# 2_Motors_V2.net
KiCad netlist of a schematic drawn in EAGLE
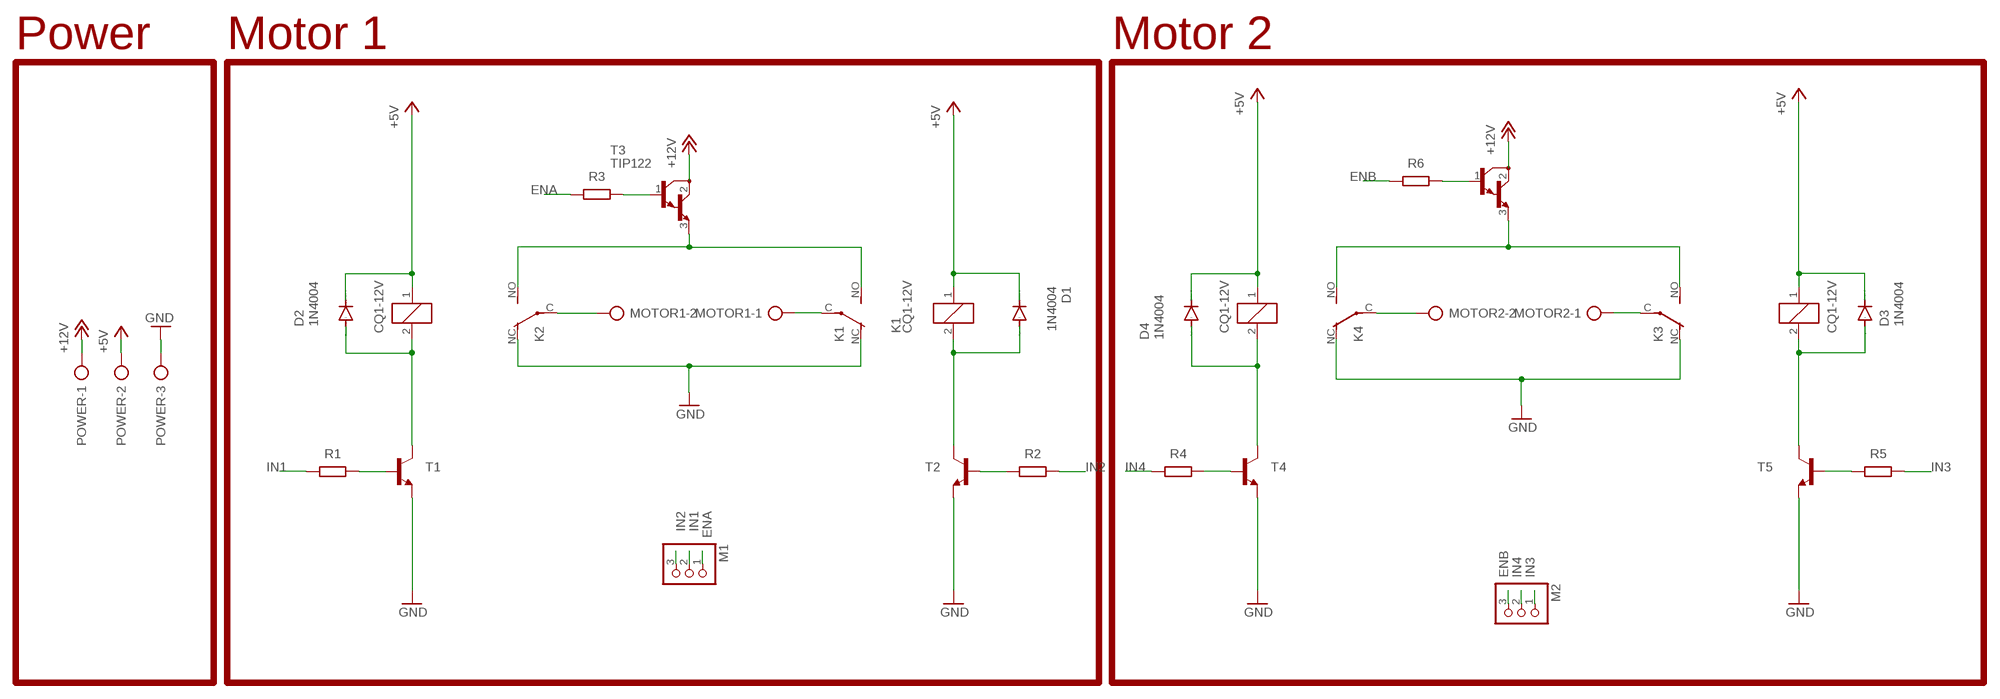
[diagram p0: schematic, sheet 1]

(export (version "E")
  (design (tool "Eeschema 10.0.6"))
  (components
    (comp (ref "D1")
      (value "1N4004")
      (footprint "eagle-import:DO41-10")
      (libsource (lib "eagle-import") (part "1N4004"))
    )
    (comp (ref "D2")
      (value "1N4004")
      (footprint "eagle-import:DO41-10")
      (libsource (lib "eagle-import") (part "1N4004"))
    )
    (comp (ref "D3")
      (value "1N4004")
      (footprint "eagle-import:DO41-10")
      (libsource (lib "eagle-import") (part "1N4004"))
    )
    (comp (ref "D4")
      (value "1N4004")
      (footprint "eagle-import:DO41-10")
      (libsource (lib "eagle-import") (part "1N4004"))
    )
    (comp (ref "K1")
      (value "CQ1-12V")
      (footprint "eagle-import:CQ1")
      (libsource (lib "eagle-import") (part "CQ1-12V"))
    )
    (comp (ref "K2")
      (value "CQ1-12V")
      (footprint "eagle-import:CQ1")
      (libsource (lib "eagle-import") (part "CQ1-12V"))
    )
    (comp (ref "K3")
      (value "CQ1-12V")
      (footprint "eagle-import:CQ1")
      (libsource (lib "eagle-import") (part "CQ1-12V"))
    )
    (comp (ref "K4")
      (value "CQ1-12V")
      (footprint "eagle-import:CQ1")
      (libsource (lib "eagle-import") (part "CQ1-12V"))
    )
    (comp (ref "M1")
      (value "PINHD-1X3")
      (footprint "eagle-import:1X03")
      (libsource (lib "eagle-import") (part "PINHD-1X3"))
    )
    (comp (ref "M2")
      (value "PINHD-1X3")
      (footprint "eagle-import:1X03")
      (libsource (lib "eagle-import") (part "PINHD-1X3"))
    )
    (comp (ref "MOTOR1")
      (value "AK300/2")
      (footprint "eagle-import:AK300_2")
      (libsource (lib "eagle-import") (part "AK300/2"))
    )
    (comp (ref "MOTOR2")
      (value "AK300/2")
      (footprint "eagle-import:AK300_2")
      (libsource (lib "eagle-import") (part "AK300/2"))
    )
    (comp (ref "POWER")
      (value "AK300/3")
      (footprint "eagle-import:AK300_3")
      (libsource (lib "eagle-import") (part "AK300/3"))
    )
    (comp (ref "R1")
      (value "4.7k")
      (footprint "eagle-import:0204_7")
      (libsource (lib "eagle-import") (part "R-EU_0204/7"))
    )
    (comp (ref "R2")
      (value "4.7k")
      (footprint "eagle-import:0204_7")
      (libsource (lib "eagle-import") (part "R-EU_0204/7"))
    )
    (comp (ref "R3")
      (value "4.7k")
      (footprint "eagle-import:0204_7")
      (libsource (lib "eagle-import") (part "R-EU_0204/7"))
    )
    (comp (ref "R4")
      (value "4.7k")
      (footprint "eagle-import:0204_7")
      (libsource (lib "eagle-import") (part "R-EU_0204/7"))
    )
    (comp (ref "R5")
      (value "4.7k")
      (footprint "eagle-import:0204_7")
      (libsource (lib "eagle-import") (part "R-EU_0204/7"))
    )
    (comp (ref "R6")
      (value "4.7k")
      (footprint "eagle-import:0204_7")
      (libsource (lib "eagle-import") (part "R-EU_0204/7"))
    )
    (comp (ref "T1")
      (value "2N2222-NPN-TO92-EBC")
      (footprint "eagle-import:TO92-EBC")
      (libsource (lib "eagle-import") (part "-NPN-TO92-EBC2N2222"))
    )
    (comp (ref "T2")
      (value "2N2222-NPN-TO92-EBC")
      (footprint "eagle-import:TO92-EBC")
      (libsource (lib "eagle-import") (part "-NPN-TO92-EBC2N2222"))
    )
    (comp (ref "T3")
      (value "TIP122")
      (footprint "eagle-import:TO220")
      (libsource (lib "eagle-import") (part "TIP122"))
    )
    (comp (ref "T4")
      (value "2N2222-NPN-TO92-EBC")
      (footprint "eagle-import:TO92-EBC")
      (libsource (lib "eagle-import") (part "-NPN-TO92-EBC2N2222"))
    )
    (comp (ref "T5")
      (value "2N2222-NPN-TO92-EBC")
      (footprint "eagle-import:TO92-EBC")
      (libsource (lib "eagle-import") (part "-NPN-TO92-EBC2N2222"))
    )
    (comp (ref "T6")
      (value "TIP122")
      (footprint "eagle-import:TO220")
      (libsource (lib "eagle-import") (part "TIP122"))
    )
  )
  (nets
    (net (code "1") (name "+5V") (class "Default")
      (node (ref "D1") (pin "C") (pinfunction "C_C") (pintype "passive"))
      (node (ref "D2") (pin "C") (pinfunction "C_C") (pintype "passive"))
      (node (ref "D3") (pin "C") (pinfunction "C_C") (pintype "passive"))
      (node (ref "D4") (pin "C") (pinfunction "C_C") (pintype "passive"))
      (node (ref "K1") (pin "1") (pinfunction "1_1") (pintype "passive"))
      (node (ref "K2") (pin "1") (pinfunction "1_1") (pintype "passive"))
      (node (ref "K3") (pin "1") (pinfunction "1_1") (pintype "passive"))
      (node (ref "K4") (pin "1") (pinfunction "1_1") (pintype "passive"))
      (node (ref "POWER") (pin "2") (pinfunction "KL_2") (pintype "passive"))
    )
    (net (code "2") (name "+12V") (class "Default")
      (node (ref "POWER") (pin "1") (pinfunction "KL_1") (pintype "passive"))
      (node (ref "T3") (pin "2") (pinfunction "C_2") (pintype "passive"))
      (node (ref "T6") (pin "2") (pinfunction "C_2") (pintype "passive"))
    )
    (net (code "3") (name "/ENA") (class "Default")
      (node (ref "M1") (pin "1") (pinfunction "1_1") (pintype "passive"))
      (node (ref "R3") (pin "2") (pinfunction "2_2") (pintype "passive"))
    )
    (net (code "4") (name "/ENB") (class "Default")
      (node (ref "M2") (pin "3") (pinfunction "3_3") (pintype "passive"))
      (node (ref "R6") (pin "2") (pinfunction "2_2") (pintype "passive"))
    )
    (net (code "5") (name "/IN1") (class "Default")
      (node (ref "M1") (pin "2") (pinfunction "2_2") (pintype "passive"))
      (node (ref "R1") (pin "1") (pinfunction "1_1") (pintype "passive"))
    )
    (net (code "6") (name "/IN2") (class "Default")
      (node (ref "M1") (pin "3") (pinfunction "3_3") (pintype "passive"))
      (node (ref "R2") (pin "1") (pinfunction "1_1") (pintype "passive"))
    )
    (net (code "7") (name "/IN3") (class "Default")
      (node (ref "M2") (pin "1") (pinfunction "1_1") (pintype "passive"))
      (node (ref "R5") (pin "1") (pinfunction "1_1") (pintype "passive"))
    )
    (net (code "8") (name "/IN4") (class "Default")
      (node (ref "M2") (pin "2") (pinfunction "2_2") (pintype "passive"))
      (node (ref "R4") (pin "2") (pinfunction "2_2") (pintype "passive"))
    )
    (net (code "9") (name "GND") (class "Default")
      (node (ref "K1") (pin "NC") (pinfunction "O_NC") (pintype "passive"))
      (node (ref "K2") (pin "NC") (pinfunction "O_NC") (pintype "passive"))
      (node (ref "K3") (pin "NC") (pinfunction "O_NC") (pintype "passive"))
      (node (ref "K4") (pin "NC") (pinfunction "O_NC") (pintype "passive"))
      (node (ref "POWER") (pin "3") (pinfunction "KL_3") (pintype "passive"))
      (node (ref "T1") (pin "E") (pinfunction "E_E") (pintype "passive"))
      (node (ref "T2") (pin "E") (pinfunction "E_E") (pintype "passive"))
      (node (ref "T4") (pin "E") (pinfunction "E_E") (pintype "passive"))
      (node (ref "T5") (pin "E") (pinfunction "E_E") (pintype "passive"))
    )
    (net (code "10") (name "Net-(D1-PadA)") (class "Default")
      (node (ref "D1") (pin "A") (pinfunction "A_A") (pintype "passive"))
      (node (ref "K1") (pin "2") (pinfunction "2_2") (pintype "passive"))
      (node (ref "T2") (pin "C") (pinfunction "C_C") (pintype "passive"))
    )
    (net (code "11") (name "Net-(D2-PadA)") (class "Default")
      (node (ref "D2") (pin "A") (pinfunction "A_A") (pintype "passive"))
      (node (ref "K2") (pin "2") (pinfunction "2_2") (pintype "passive"))
      (node (ref "T1") (pin "C") (pinfunction "C_C") (pintype "passive"))
    )
    (net (code "12") (name "Net-(D3-PadA)") (class "Default")
      (node (ref "D3") (pin "A") (pinfunction "A_A") (pintype "passive"))
      (node (ref "K3") (pin "2") (pinfunction "2_2") (pintype "passive"))
      (node (ref "T5") (pin "C") (pinfunction "C_C") (pintype "passive"))
    )
    (net (code "13") (name "Net-(D4-PadA)") (class "Default")
      (node (ref "D4") (pin "A") (pinfunction "A_A") (pintype "passive"))
      (node (ref "K4") (pin "2") (pinfunction "2_2") (pintype "passive"))
      (node (ref "T4") (pin "C") (pinfunction "C_C") (pintype "passive"))
    )
    (net (code "14") (name "Net-(K1B-P)") (class "Default")
      (node (ref "K1") (pin "C") (pinfunction "P_C") (pintype "passive"))
      (node (ref "MOTOR1") (pin "1") (pinfunction "KL_1") (pintype "passive"))
    )
    (net (code "15") (name "Net-(K1B-S)") (class "Default")
      (node (ref "K1") (pin "NO") (pinfunction "S_NO") (pintype "passive"))
      (node (ref "K2") (pin "NO") (pinfunction "S_NO") (pintype "passive"))
      (node (ref "T3") (pin "3") (pinfunction "E_3") (pintype "passive"))
    )
    (net (code "16") (name "Net-(K2B-P)") (class "Default")
      (node (ref "K2") (pin "C") (pinfunction "P_C") (pintype "passive"))
      (node (ref "MOTOR1") (pin "2") (pinfunction "KL_2") (pintype "passive"))
    )
    (net (code "17") (name "Net-(K3B-P)") (class "Default")
      (node (ref "K3") (pin "C") (pinfunction "P_C") (pintype "passive"))
      (node (ref "MOTOR2") (pin "1") (pinfunction "KL_1") (pintype "passive"))
    )
    (net (code "18") (name "Net-(K3B-S)") (class "Default")
      (node (ref "K3") (pin "NO") (pinfunction "S_NO") (pintype "passive"))
      (node (ref "K4") (pin "NO") (pinfunction "S_NO") (pintype "passive"))
      (node (ref "T6") (pin "3") (pinfunction "E_3") (pintype "passive"))
    )
    (net (code "19") (name "Net-(K4B-P)") (class "Default")
      (node (ref "K4") (pin "C") (pinfunction "P_C") (pintype "passive"))
      (node (ref "MOTOR2") (pin "2") (pinfunction "KL_2") (pintype "passive"))
    )
    (net (code "20") (name "Net-(R1-Pad2)") (class "Default")
      (node (ref "R1") (pin "2") (pinfunction "2_2") (pintype "passive"))
      (node (ref "T1") (pin "B") (pinfunction "B_B") (pintype "passive"))
    )
    (net (code "21") (name "Net-(R2-Pad2)") (class "Default")
      (node (ref "R2") (pin "2") (pinfunction "2_2") (pintype "passive"))
      (node (ref "T2") (pin "B") (pinfunction "B_B") (pintype "passive"))
    )
    (net (code "22") (name "Net-(R4-Pad1)") (class "Default")
      (node (ref "R4") (pin "1") (pinfunction "1_1") (pintype "passive"))
      (node (ref "T4") (pin "B") (pinfunction "B_B") (pintype "passive"))
    )
    (net (code "23") (name "Net-(R5-Pad2)") (class "Default")
      (node (ref "R5") (pin "2") (pinfunction "2_2") (pintype "passive"))
      (node (ref "T5") (pin "B") (pinfunction "B_B") (pintype "passive"))
    )
    (net (code "24") (name "Net-(T3-B)") (class "Default")
      (node (ref "R3") (pin "1") (pinfunction "1_1") (pintype "passive"))
      (node (ref "T3") (pin "1") (pinfunction "B_1") (pintype "passive"))
    )
    (net (code "25") (name "Net-(T6-B)") (class "Default")
      (node (ref "R6") (pin "1") (pinfunction "1_1") (pintype "passive"))
      (node (ref "T6") (pin "1") (pinfunction "B_1") (pintype "passive"))
    )
  )
)
